# peripherals.net
KiCad netlist of a schematic drawn in Altium Designer
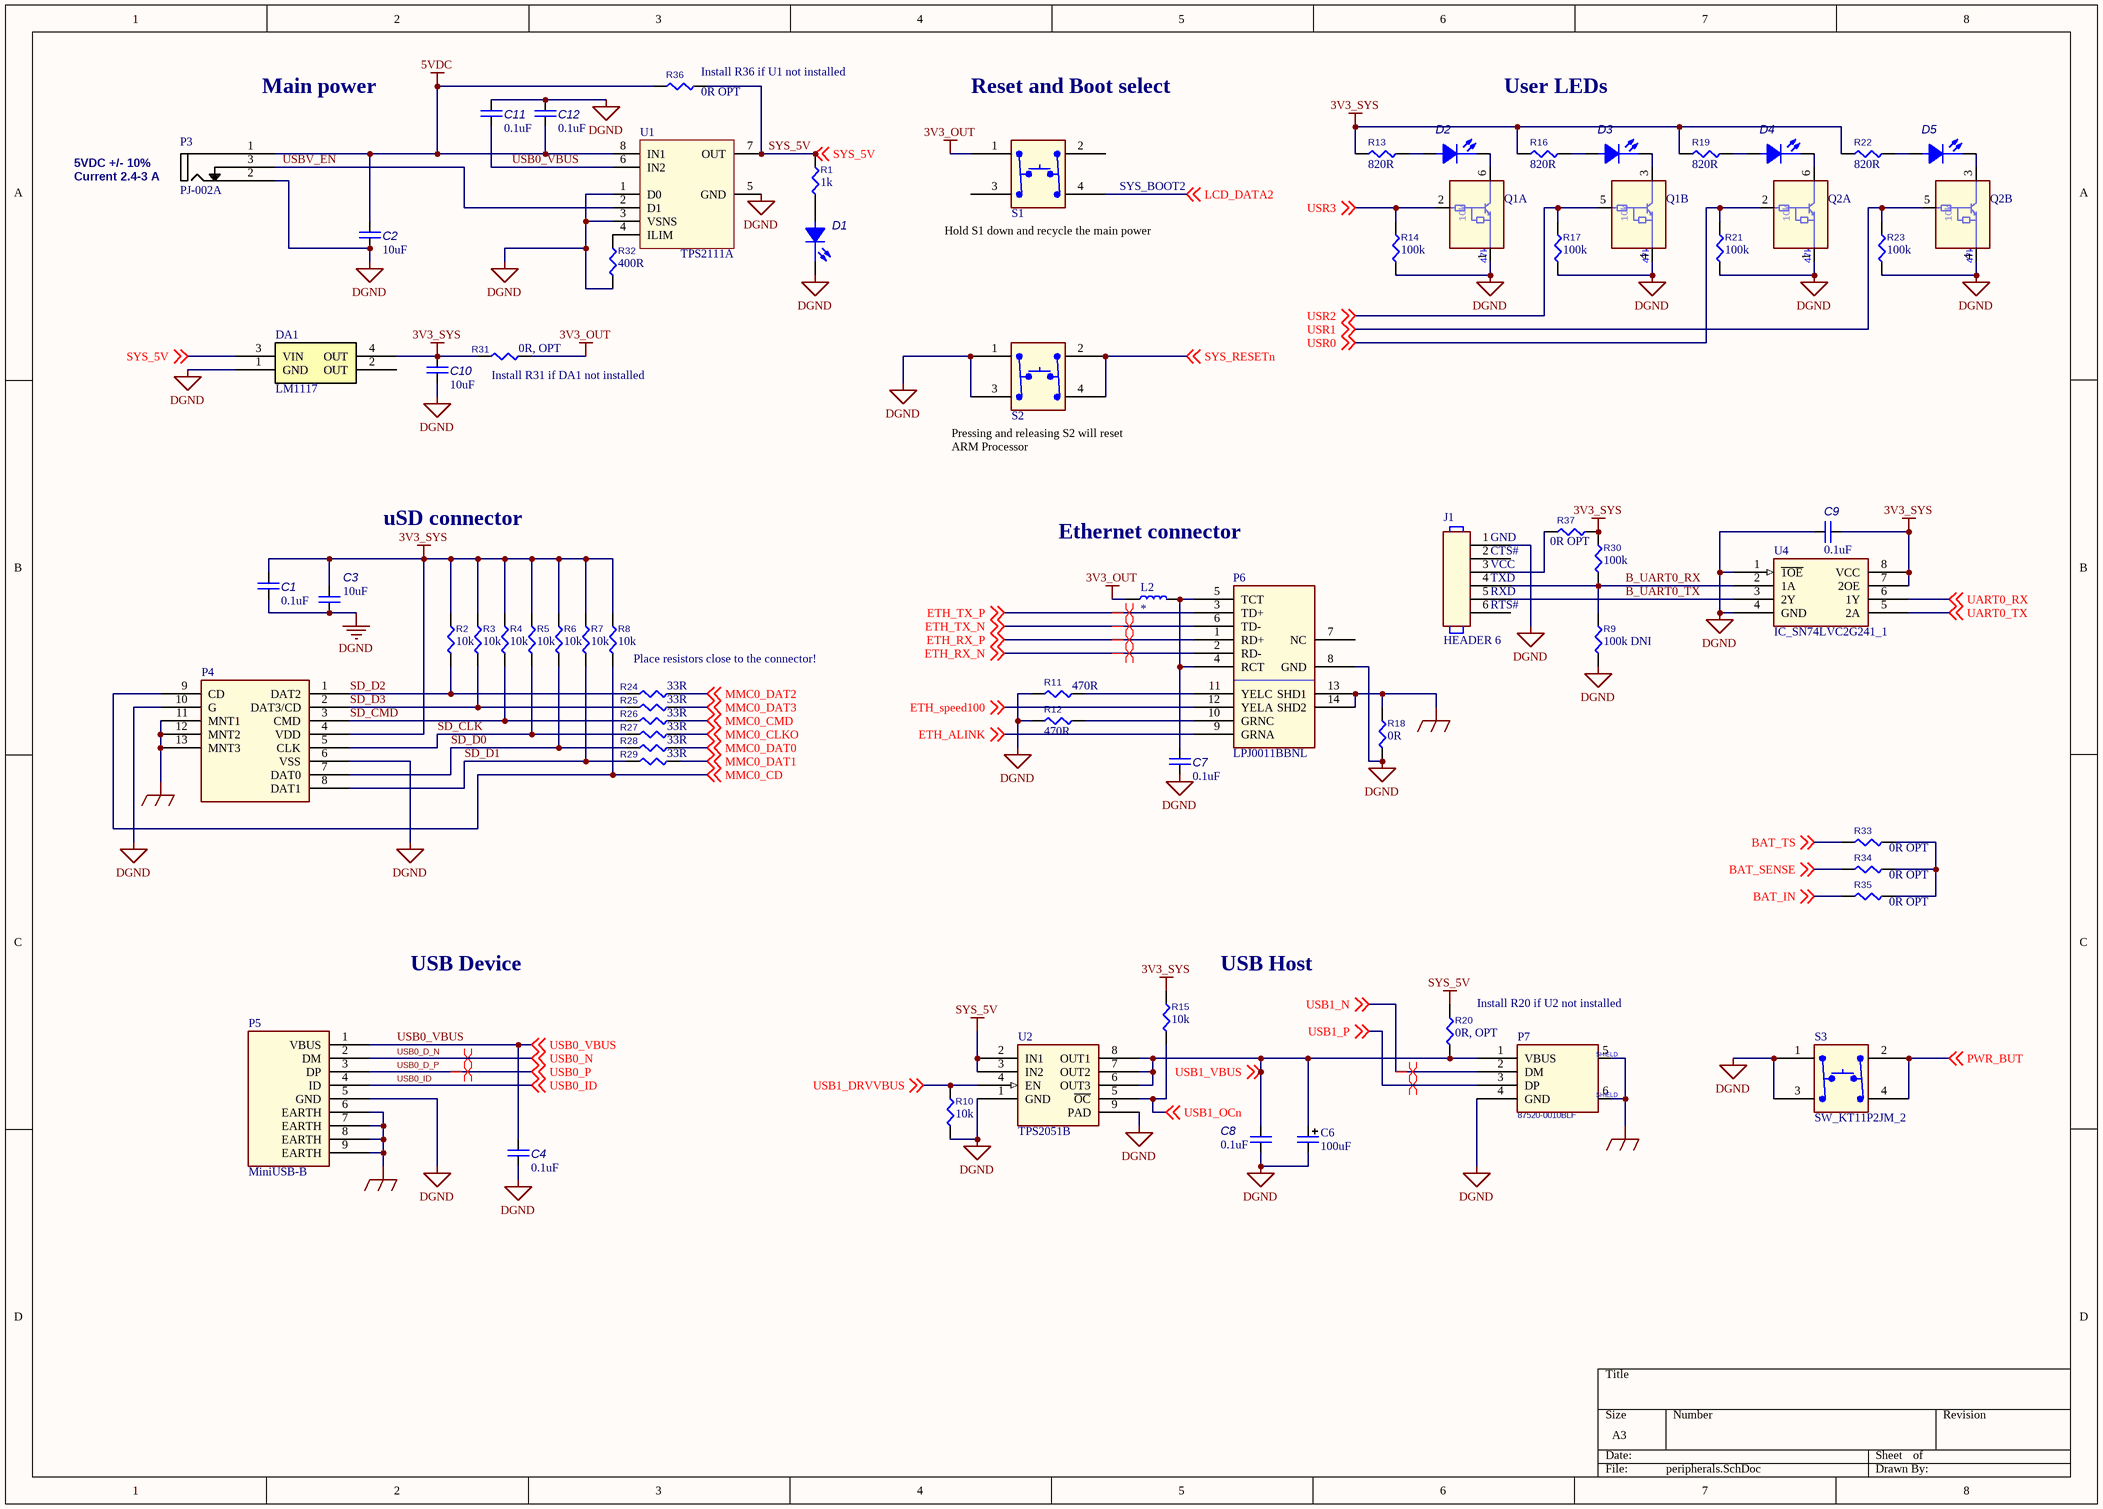
[diagram p0: peripherals.SchDoc]

(export (version "E")
  (design (tool "Eeschema 10.0.6"))
  (components
    (comp (ref "C1")
      (value "0.1uF")
      (footprint "CC1608-0603")
      (description "C0603")
      (libsource (lib "am335x-base") (part "C0603"))
    )
    (comp (ref "C2")
      (value "10uF")
      (footprint "CC2012-0805")
      (description "C0805")
      (libsource (lib "am335x-base") (part "C0805"))
    )
    (comp (ref "C3")
      (value "10uF")
      (footprint "CC2012-0805")
      (description "C0805")
      (libsource (lib "am335x-base") (part "C0805"))
    )
    (comp (ref "C4")
      (value "0.1uF")
      (footprint "CC1608-0603")
      (description "C0603")
      (libsource (lib "am335x-base") (part "C0603"))
    )
    (comp (ref "C6")
      (value "100uF")
      (footprint "Cap_C")
      (description "Tantalum Capacitor Case C")
      (fields (field (name "Comment") "Cap_C"))
      (libsource (lib "am335x-base") (part "Cap_C"))
    )
    (comp (ref "C7")
      (value "0.1uF")
      (footprint "CC1608-0603")
      (description "C0603")
      (libsource (lib "am335x-base") (part "C0603"))
    )
    (comp (ref "C8")
      (value "0.1uF")
      (footprint "CC1608-0603")
      (description "C0603")
      (libsource (lib "am335x-base") (part "C0603"))
    )
    (comp (ref "C9")
      (value "0.1uF")
      (footprint "CC1608-0603")
      (description "C0603")
      (libsource (lib "usomiq-base") (part "C0603"))
    )
    (comp (ref "C10")
      (value "10uF")
      (footprint "CC2012-0805")
      (description "C0805")
      (libsource (lib "am335x-base") (part "C0805"))
    )
    (comp (ref "C11")
      (value "0.1uF")
      (footprint "CC1608-0603")
      (description "C0603")
      (libsource (lib "am335x-base") (part "C0603"))
    )
    (comp (ref "C12")
      (value "0.1uF")
      (footprint "CC1608-0603")
      (description "C0603")
      (libsource (lib "am335x-base") (part "C0603"))
    )
    (comp (ref "D1")
      (value "LED0805")
      (footprint "LED0805")
      (description "LED 0805")
      (libsource (lib "am335x-base") (part "LED0805"))
    )
    (comp (ref "D2")
      (value "LED0805")
      (footprint "LED0805")
      (description "LED 0805")
      (libsource (lib "am335x-base") (part "LED0805"))
    )
    (comp (ref "D3")
      (value "LED0805")
      (footprint "LED0805")
      (description "LED 0805")
      (libsource (lib "am335x-base") (part "LED0805"))
    )
    (comp (ref "D4")
      (value "LED0805")
      (footprint "LED0805")
      (description "LED 0805")
      (libsource (lib "am335x-base") (part "LED0805"))
    )
    (comp (ref "D5")
      (value "LED0805")
      (footprint "LED0805")
      (description "LED 0805")
      (libsource (lib "am335x-base") (part "LED0805"))
    )
    (comp (ref "DA1")
      (value "LM1117")
      (footprint "SOT230P700X160-4N")
      (description "800mA Low-Dropout Linear Regulator")
      (fields (field (name "MANUFACTURER") "National"))
      (libsource (lib "usomiq-base") (part "LM1117"))
    )
    (comp (ref "J1")
      (value "HEADER 6")
      (footprint "DIP6")
      (description "CONN HEADER 6POS, VERTICAL,  .100 STR TIN")
      (fields (field (name "MFR") "FCI"))
      (libsource (lib "usomiq-base") (part "HEADER 6"))
    )
    (comp (ref "L2")
      (value "BLM18A-FB")
      (footprint "CHIP0603")
      (description "Chip EMIFILr Inductor Type")
      (fields (field (name "MANUFACTURER") "Murata") (field (name "MAN P/N") "*"))
      (libsource (lib "am335x-base") (part "BLM18A-FB"))
    )
    (comp (ref "P3")
      (value "PJ-002A")
      (footprint "PJ-002A")
      (description "DC POWER JACK")
      (fields (field (name "MANUFACTURER") "CIU Inc"))
      (libsource (lib "omap") (part "PJ-002A"))
    )
    (comp (ref "P4")
      (value "~")
      (footprint "TFC08WP01F-A-R1K-H")
      (description "Connector for microSD™ Card (Push-push Type)")
      (fields (field (name "MFR") "AUK Contractors Co, LTD"))
      (libsource (lib "usomiq-base") (part "TFC08WP01F-R1K-H-CN"))
    )
    (comp (ref "P5")
      (value "MiniUSB-B")
      (footprint "MINI-USB-B5 SMT")
      (description "Mini USB Type B CONNECTOR")
      (fields (field (name "MFR") "Hirose"))
      (libsource (lib "usomiq-base") (part "MiniUSB-B"))
    )
    (comp (ref "P6")
      (value "CONN_RJ45_MAG_WE_0")
      (footprint "TRJ0011ABNL")
      (description "RJ-45 10/100 W/Magnetics")
      (fields (field (name "MFR") "Link PP") (field (name "P/N") "LPJ0011BBNL"))
      (libsource (lib "am335x-base") (part "CONN_RJ45_MAG_WE_0"))
    )
    (comp (ref "P7")
      (value "CONN_54819-0578_2")
      (footprint "USB2.5-2H4C")
      (description "USB Type A Connectors")
      (fields (field (name "P/N") "87520-0010BLF") (field (name "MFR") "FCI"))
      (libsource (lib "am335x-base") (part "CONN_54819-0578_2"))
    )
    (comp (ref "Q1")
      (value "RN1907")
      (footprint "SOT363-6L")
      (description "Transistor Silicon NPN")
      (fields (field (name "MFR") "ONS"))
      (libsource (lib "usomiq-base") (part "RN1907"))
    )
    (comp (ref "Q2")
      (value "RN1907")
      (footprint "SOT363-6L")
      (description "Transistor Silicon NPN")
      (fields (field (name "MFR") "ONS"))
      (libsource (lib "usomiq-base") (part "RN1907"))
    )
    (comp (ref "R1")
      (value "1k")
      (footprint "RESC1608X55N")
      (description "R0603")
      (libsource (lib "am335x-base") (part "R0603"))
    )
    (comp (ref "R2")
      (value "10k")
      (footprint "RESC1608X55N")
      (description "R0603")
      (libsource (lib "am335x-base") (part "R0603"))
    )
    (comp (ref "R3")
      (value "10k")
      (footprint "RESC1608X55N")
      (description "R0603")
      (libsource (lib "am335x-base") (part "R0603"))
    )
    (comp (ref "R4")
      (value "10k")
      (footprint "RESC1608X55N")
      (description "R0603")
      (libsource (lib "am335x-base") (part "R0603"))
    )
    (comp (ref "R5")
      (value "10k")
      (footprint "RESC1608X55N")
      (description "R0603")
      (libsource (lib "am335x-base") (part "R0603"))
    )
    (comp (ref "R6")
      (value "10k")
      (footprint "RESC1608X55N")
      (description "R0603")
      (libsource (lib "am335x-base") (part "R0603"))
    )
    (comp (ref "R7")
      (value "10k")
      (footprint "RESC1608X55N")
      (description "R0603")
      (libsource (lib "am335x-base") (part "R0603"))
    )
    (comp (ref "R8")
      (value "10k")
      (footprint "RESC1608X55N")
      (description "R0603")
      (libsource (lib "am335x-base") (part "R0603"))
    )
    (comp (ref "R9")
      (value "100k DNI")
      (footprint "RESC1608X55N")
      (description "R0603")
      (libsource (lib "am335x-base") (part "R0603"))
    )
    (comp (ref "R10")
      (value "10k")
      (footprint "RESC1608X55N")
      (description "R0603")
      (libsource (lib "am335x-base") (part "R0603"))
    )
    (comp (ref "R11")
      (value "470R")
      (footprint "RESC1608X55N")
      (description "R0603")
      (libsource (lib "am335x-base") (part "R0603"))
    )
    (comp (ref "R12")
      (value "470R")
      (footprint "RESC1608X55N")
      (description "R0603")
      (libsource (lib "am335x-base") (part "R0603"))
    )
    (comp (ref "R13")
      (value "820R")
      (footprint "RESC1608X55N")
      (description "R0603")
      (libsource (lib "am335x-base") (part "R0603"))
    )
    (comp (ref "R14")
      (value "100k")
      (footprint "RESC1608X55N")
      (description "R0603")
      (libsource (lib "am335x-base") (part "R0603"))
    )
    (comp (ref "R15")
      (value "10k")
      (footprint "RESC1608X55N")
      (description "R0603")
      (libsource (lib "am335x-base") (part "R0603"))
    )
    (comp (ref "R16")
      (value "820R")
      (footprint "RESC1608X55N")
      (description "R0603")
      (libsource (lib "am335x-base") (part "R0603"))
    )
    (comp (ref "R17")
      (value "100k")
      (footprint "RESC1608X55N")
      (description "R0603")
      (libsource (lib "am335x-base") (part "R0603"))
    )
    (comp (ref "R18")
      (value "0R")
      (footprint "RESC1608X55N")
      (description "R0603")
      (libsource (lib "am335x-base") (part "R0603"))
    )
    (comp (ref "R19")
      (value "820R")
      (footprint "RESC1608X55N")
      (description "R0603")
      (libsource (lib "am335x-base") (part "R0603"))
    )
    (comp (ref "R20")
      (value "0R, OPT")
      (footprint "RESC1608X55N")
      (description "R0603")
      (libsource (lib "am335x-base") (part "R0603"))
    )
    (comp (ref "R21")
      (value "100k")
      (footprint "RESC1608X55N")
      (description "R0603")
      (libsource (lib "am335x-base") (part "R0603"))
    )
    (comp (ref "R22")
      (value "820R")
      (footprint "RESC1608X55N")
      (description "R0603")
      (libsource (lib "am335x-base") (part "R0603"))
    )
    (comp (ref "R23")
      (value "100k")
      (footprint "RESC1608X55N")
      (description "R0603")
      (libsource (lib "am335x-base") (part "R0603"))
    )
    (comp (ref "R24")
      (value "33R")
      (footprint "RESC1608X55N")
      (description "R0603")
      (libsource (lib "usomiq-base") (part "R0603"))
    )
    (comp (ref "R25")
      (value "33R")
      (footprint "RESC1608X55N")
      (description "R0603")
      (libsource (lib "usomiq-base") (part "R0603"))
    )
    (comp (ref "R26")
      (value "33R")
      (footprint "RESC1608X55N")
      (description "R0603")
      (libsource (lib "usomiq-base") (part "R0603"))
    )
    (comp (ref "R27")
      (value "33R")
      (footprint "RESC1608X55N")
      (description "R0603")
      (libsource (lib "usomiq-base") (part "R0603"))
    )
    (comp (ref "R28")
      (value "33R")
      (footprint "RESC1608X55N")
      (description "R0603")
      (libsource (lib "usomiq-base") (part "R0603"))
    )
    (comp (ref "R29")
      (value "33R")
      (footprint "RESC1608X55N")
      (description "R0603")
      (libsource (lib "usomiq-base") (part "R0603"))
    )
    (comp (ref "R30")
      (value "100k")
      (footprint "RESC1608X55N")
      (description "R0603")
      (libsource (lib "am335x-base") (part "R0603"))
    )
    (comp (ref "R31")
      (value "0R, OPT")
      (footprint "RESC1608X55N")
      (description "R0603")
      (libsource (lib "usomiq-base") (part "R0603"))
    )
    (comp (ref "R32")
      (value "400R")
      (footprint "RESC1608X55N")
      (description "R0603")
      (libsource (lib "usomiq-base") (part "R0603"))
    )
    (comp (ref "R33")
      (value "0R OPT")
      (footprint "RESC1608X55N")
      (description "R0603")
      (libsource (lib "usomiq-base") (part "R0603"))
    )
    (comp (ref "R34")
      (value "0R OPT")
      (footprint "RESC1608X55N")
      (description "R0603")
      (libsource (lib "usomiq-base") (part "R0603"))
    )
    (comp (ref "R35")
      (value "0R OPT")
      (footprint "RESC1608X55N")
      (description "R0603")
      (libsource (lib "usomiq-base") (part "R0603"))
    )
    (comp (ref "R36")
      (value "0R OPT")
      (footprint "RESC1608X55N")
      (description "R0603")
      (libsource (lib "usomiq-base") (part "R0603"))
    )
    (comp (ref "R37")
      (value "0R OPT")
      (footprint "RESC1608X55N")
      (description "R0603")
      (libsource (lib "usomiq-base") (part "R0603"))
    )
    (comp (ref "S1")
      (value "SW_KT11P2JM_2")
      (footprint "KMR231GLFS")
      (description "SMD button")
      (fields (field (name "MFR") "C&K Components"))
      (libsource (lib "usomiq-base") (part "SW_KT11P2JM_2"))
    )
    (comp (ref "S2")
      (value "SW_KT11P2JM_2")
      (footprint "KMR231GLFS")
      (description "SMD button")
      (fields (field (name "MFR") "C&K Components"))
      (libsource (lib "usomiq-base") (part "SW_KT11P2JM_2"))
    )
    (comp (ref "S3")
      (value "SW_KT11P2JM_2")
      (footprint "KMR231GLFS")
      (description "SMD button")
      (fields (field (name "MFR") "C&K Components"))
      (libsource (lib "usomiq-base") (part "SW_KT11P2JM_2"))
    )
    (comp (ref "U1")
      (value "TPS211xA")
      (footprint "TSSOP-8")
      (description "Single Channel, Current-Limited USB Power Distribution Switch")
      (fields (field (name "MANUFACTURER") "TI") (field (name "P/N") "TPS2111A"))
      (libsource (lib "usomiq-base") (part "TPS211xA"))
    )
    (comp (ref "U2")
      (value "TPS2051B")
      (footprint "R-PDSO-G8")
      (description "CURRENT-LIMITED, POWER-DISTRIBUTION SWITCHES")
      (fields (field (name "MFR") "TI"))
      (libsource (lib "usomiq-base") (part "TPS2051B"))
    )
    (comp (ref "U4")
      (value "IC_SN74LVC2G241_1")
      (footprint "SOP127P600-8N")
      (description "Dual Buffer/Driver With 3-State Outputs")
      (fields (field (name "MFR") "TI"))
      (libsource (lib "usomiq-base") (part "IC_SN74LVC2G241_1"))
    )
  )
  (nets
    (net (code "1") (name "/B_UART0_RX") (class "Default")
      (node (ref "J1") (pin "4") (pinfunction "4_4") (pintype "passive"))
      (node (ref "R30") (pin "1") (pinfunction "1_1") (pintype "passive"))
      (node (ref "R9") (pin "2") (pinfunction "2_2") (pintype "passive"))
      (node (ref "U4") (pin "2") (pinfunction "1A_2") (pintype "passive"))
    )
    (net (code "2") (name "/B_UART0_TX") (class "Default")
      (node (ref "J1") (pin "5") (pinfunction "5_5") (pintype "passive"))
      (node (ref "U4") (pin "3") (pinfunction "2Y_3") (pintype "passive"))
    )
    (net (code "3") (name "/SD_CLK") (class "Default")
      (node (ref "P4") (pin "5") (pinfunction "CLK_5") (pintype "passive"))
      (node (ref "R27") (pin "1") (pinfunction "1_1") (pintype "passive"))
      (node (ref "R5") (pin "1") (pinfunction "1_1") (pintype "passive"))
    )
    (net (code "4") (name "/SD_CMD") (class "Default")
      (node (ref "P4") (pin "3") (pinfunction "CMD_3") (pintype "passive"))
      (node (ref "R26") (pin "1") (pinfunction "1_1") (pintype "passive"))
      (node (ref "R4") (pin "1") (pinfunction "1_1") (pintype "passive"))
    )
    (net (code "5") (name "/SD_D0") (class "Default")
      (node (ref "P4") (pin "7") (pinfunction "DAT0_7") (pintype "passive"))
      (node (ref "R28") (pin "1") (pinfunction "1_1") (pintype "passive"))
      (node (ref "R6") (pin "1") (pinfunction "1_1") (pintype "passive"))
    )
    (net (code "6") (name "/SD_D1") (class "Default")
      (node (ref "P4") (pin "8") (pinfunction "DAT1_8") (pintype "passive"))
      (node (ref "R29") (pin "1") (pinfunction "1_1") (pintype "passive"))
      (node (ref "R7") (pin "1") (pinfunction "1_1") (pintype "passive"))
    )
    (net (code "7") (name "/SD_D2") (class "Default")
      (node (ref "P4") (pin "1") (pinfunction "DAT2_1") (pintype "passive"))
      (node (ref "R2") (pin "1") (pinfunction "1_1") (pintype "passive"))
      (node (ref "R24") (pin "1") (pinfunction "1_1") (pintype "passive"))
    )
    (net (code "8") (name "/SD_D3") (class "Default")
      (node (ref "P4") (pin "2") (pinfunction "DAT3/CD_2") (pintype "passive"))
      (node (ref "R25") (pin "1") (pinfunction "1_1") (pintype "passive"))
      (node (ref "R3") (pin "1") (pinfunction "1_1") (pintype "passive"))
    )
    (net (code "9") (name "/USBV_EN") (class "Default")
      (node (ref "P3") (pin "3") (pinfunction "LEFT_3") (pintype "passive"))
      (node (ref "U1") (pin "2") (pinfunction "D1_2") (pintype "passive"))
    )
    (net (code "10") (name "3V3_OUT") (class "Default")
      (node (ref "L2") (pin "1") (pinfunction "1_1") (pintype "passive"))
      (node (ref "R31") (pin "2") (pinfunction "2_2") (pintype "passive"))
      (node (ref "S1") (pin "1") (pinfunction "A1_1") (pintype "passive"))
    )
    (net (code "11") (name "3V3_SYS") (class "Default")
      (node (ref "C1") (pin "1") (pinfunction "1_1") (pintype "passive"))
      (node (ref "C10") (pin "2") (pinfunction "2_2") (pintype "passive"))
      (node (ref "C3") (pin "2") (pinfunction "2_2") (pintype "passive"))
      (node (ref "C9") (pin "2") (pinfunction "2_2") (pintype "passive"))
      (node (ref "DA1") (pin "4") (pinfunction "OUT_4") (pintype "power_in"))
      (node (ref "P4") (pin "4") (pinfunction "VDD_4") (pintype "power_in"))
      (node (ref "R13") (pin "2") (pinfunction "2_2") (pintype "passive"))
      (node (ref "R15") (pin "2") (pinfunction "2_2") (pintype "passive"))
      (node (ref "R16") (pin "2") (pinfunction "2_2") (pintype "passive"))
      (node (ref "R19") (pin "2") (pinfunction "2_2") (pintype "passive"))
      (node (ref "R2") (pin "2") (pinfunction "2_2") (pintype "passive"))
      (node (ref "R22") (pin "2") (pinfunction "2_2") (pintype "passive"))
      (node (ref "R3") (pin "2") (pinfunction "2_2") (pintype "passive"))
      (node (ref "R30") (pin "2") (pinfunction "2_2") (pintype "passive"))
      (node (ref "R31") (pin "1") (pinfunction "1_1") (pintype "passive"))
      (node (ref "R37") (pin "2") (pinfunction "2_2") (pintype "passive"))
      (node (ref "R4") (pin "2") (pinfunction "2_2") (pintype "passive"))
      (node (ref "R5") (pin "2") (pinfunction "2_2") (pintype "passive"))
      (node (ref "R6") (pin "2") (pinfunction "2_2") (pintype "passive"))
      (node (ref "R7") (pin "2") (pinfunction "2_2") (pintype "passive"))
      (node (ref "R8") (pin "2") (pinfunction "2_2") (pintype "passive"))
      (node (ref "U4") (pin "7") (pinfunction "2OE_7") (pintype "passive"))
      (node (ref "U4") (pin "8") (pinfunction "VCC_8") (pintype "power_in"))
    )
    (net (code "12") (name "5VDC") (class "Default")
      (node (ref "C12") (pin "2") (pinfunction "2_2") (pintype "passive"))
      (node (ref "C2") (pin "2") (pinfunction "2_2") (pintype "passive"))
      (node (ref "P3") (pin "1") (pinfunction "GND_1") (pintype "passive"))
      (node (ref "R36") (pin "1") (pinfunction "1_1") (pintype "passive"))
      (node (ref "U1") (pin "8") (pinfunction "IN1_8") (pintype "passive"))
    )
    (net (code "13") (name "BAT_IN") (class "Default")
      (node (ref "R35") (pin "1") (pinfunction "1_1") (pintype "passive"))
    )
    (net (code "14") (name "BAT_SENSE") (class "Default")
      (node (ref "R34") (pin "1") (pinfunction "1_1") (pintype "passive"))
    )
    (net (code "15") (name "BAT_TS") (class "Default")
      (node (ref "R33") (pin "1") (pinfunction "1_1") (pintype "passive"))
    )
    (net (code "16") (name "DGND") (class "Default")
      (node (ref "C1") (pin "2") (pinfunction "2_2") (pintype "passive"))
      (node (ref "C10") (pin "1") (pinfunction "1_1") (pintype "passive"))
      (node (ref "C11") (pin "1") (pinfunction "1_1") (pintype "passive"))
      (node (ref "C12") (pin "1") (pinfunction "1_1") (pintype "passive"))
      (node (ref "C2") (pin "1") (pinfunction "1_1") (pintype "passive"))
      (node (ref "C3") (pin "1") (pinfunction "1_1") (pintype "passive"))
      (node (ref "C4") (pin "2") (pinfunction "2_2") (pintype "passive"))
      (node (ref "C6") (pin "2") (pinfunction "2_2") (pintype "passive"))
      (node (ref "C7") (pin "2") (pinfunction "2_2") (pintype "passive"))
      (node (ref "C8") (pin "1") (pinfunction "1_1") (pintype "passive"))
      (node (ref "C9") (pin "1") (pinfunction "1_1") (pintype "passive"))
      (node (ref "D1") (pin "2") (pinfunction "C_2") (pintype "passive"))
      (node (ref "DA1") (pin "1") (pinfunction "GND_1") (pintype "power_in"))
      (node (ref "J1") (pin "1") (pinfunction "1_1") (pintype "passive"))
      (node (ref "P3") (pin "2") (pinfunction "RIGHT_2") (pintype "passive"))
      (node (ref "P4") (pin "10") (pinfunction "G_10") (pintype "passive"))
      (node (ref "P4") (pin "6") (pinfunction "VSS_6") (pintype "power_in"))
      (node (ref "P5") (pin "5") (pinfunction "GND_5") (pintype "power_in"))
      (node (ref "P6") (pin "8") (pinfunction "GND_8") (pintype "passive"))
      (node (ref "P7") (pin "4") (pinfunction "GND_4") (pintype "passive"))
      (node (ref "Q1") (pin "1") (pinfunction "4_1") (pintype "passive"))
      (node (ref "Q1") (pin "4") (pinfunction "4_4") (pintype "passive"))
      (node (ref "Q2") (pin "1") (pinfunction "4_1") (pintype "passive"))
      (node (ref "Q2") (pin "4") (pinfunction "4_4") (pintype "passive"))
      (node (ref "R10") (pin "1") (pinfunction "1_1") (pintype "passive"))
      (node (ref "R11") (pin "1") (pinfunction "1_1") (pintype "passive"))
      (node (ref "R12") (pin "1") (pinfunction "1_1") (pintype "passive"))
      (node (ref "R14") (pin "1") (pinfunction "1_1") (pintype "passive"))
      (node (ref "R17") (pin "1") (pinfunction "1_1") (pintype "passive"))
      (node (ref "R18") (pin "1") (pinfunction "1_1") (pintype "passive"))
      (node (ref "R21") (pin "1") (pinfunction "1_1") (pintype "passive"))
      (node (ref "R23") (pin "1") (pinfunction "1_1") (pintype "passive"))
      (node (ref "R32") (pin "2") (pinfunction "2_2") (pintype "passive"))
      (node (ref "R9") (pin "1") (pinfunction "1_1") (pintype "passive"))
      (node (ref "S2") (pin "1") (pinfunction "A1_1") (pintype "passive"))
      (node (ref "S2") (pin "3") (pinfunction "A2_3") (pintype "passive"))
      (node (ref "S3") (pin "1") (pinfunction "A1_1") (pintype "passive"))
      (node (ref "S3") (pin "3") (pinfunction "A2_3") (pintype "passive"))
      (node (ref "U1") (pin "1") (pinfunction "D0_1") (pintype "passive"))
      (node (ref "U1") (pin "3") (pinfunction "VSNS_3") (pintype "passive"))
      (node (ref "U1") (pin "5") (pinfunction "GND_5") (pintype "passive"))
      (node (ref "U2") (pin "1") (pinfunction "GND_1") (pintype "power_in"))
      (node (ref "U2") (pin "9") (pinfunction "PAD_9") (pintype "passive"))
      (node (ref "U4") (pin "1") (pinfunction "~{1OE}_1") (pintype "input"))
      (node (ref "U4") (pin "4") (pinfunction "GND_4") (pintype "power_in"))
    )
    (net (code "17") (name "EARTH") (class "Default")
      (node (ref "P4") (pin "11") (pinfunction "MNT1_11") (pintype "passive"))
      (node (ref "P4") (pin "12") (pinfunction "MNT2_12") (pintype "passive"))
      (node (ref "P4") (pin "13") (pinfunction "MNT3_13") (pintype "passive"))
      (node (ref "P5") (pin "6") (pinfunction "EARTH_6") (pintype "passive"))
      (node (ref "P5") (pin "7") (pinfunction "EARTH_7") (pintype "passive"))
      (node (ref "P5") (pin "8") (pinfunction "EARTH_8") (pintype "passive"))
      (node (ref "P5") (pin "9") (pinfunction "EARTH_9") (pintype "passive"))
      (node (ref "P6") (pin "13") (pinfunction "SHD1_13") (pintype "passive"))
      (node (ref "P6") (pin "14") (pinfunction "SHD2_14") (pintype "passive"))
      (node (ref "P7") (pin "5") (pinfunction "SHELD1_5") (pintype "passive"))
      (node (ref "P7") (pin "6") (pinfunction "PAD4_6") (pintype "passive"))
      (node (ref "R18") (pin "2") (pinfunction "2_2") (pintype "passive"))
    )
    (net (code "18") (name "ETH_ALINK") (class "Default")
      (node (ref "P6") (pin "9") (pinfunction "GRNA_9") (pintype "passive"))
    )
    (net (code "19") (name "ETH_RX_N") (class "Default")
      (node (ref "P6") (pin "2") (pinfunction "RD-_2") (pintype "passive"))
    )
    (net (code "20") (name "ETH_RX_P") (class "Default")
      (node (ref "P6") (pin "1") (pinfunction "RD+_1") (pintype "passive"))
    )
    (net (code "21") (name "ETH_TX_N") (class "Default")
      (node (ref "P6") (pin "6") (pinfunction "TD-_6") (pintype "passive"))
    )
    (net (code "22") (name "ETH_TX_P") (class "Default")
      (node (ref "P6") (pin "3") (pinfunction "TD+_3") (pintype "passive"))
    )
    (net (code "23") (name "ETH_speed100") (class "Default")
      (node (ref "P6") (pin "12") (pinfunction "YELA_12") (pintype "passive"))
    )
    (net (code "24") (name "LCD_DATA2") (class "Default")
      (node (ref "S1") (pin "4") (pinfunction "B2_4") (pintype "passive"))
    )
    (net (code "25") (name "MMC0_CD") (class "Default")
      (node (ref "P4") (pin "9") (pinfunction "CD_9") (pintype "passive"))
      (node (ref "R8") (pin "1") (pinfunction "1_1") (pintype "passive"))
    )
    (net (code "26") (name "MMC0_CLKO") (class "Default")
      (node (ref "R27") (pin "2") (pinfunction "2_2") (pintype "passive"))
    )
    (net (code "27") (name "MMC0_CMD") (class "Default")
      (node (ref "R26") (pin "2") (pinfunction "2_2") (pintype "passive"))
    )
    (net (code "28") (name "MMC0_DAT0") (class "Default")
      (node (ref "R28") (pin "2") (pinfunction "2_2") (pintype "passive"))
    )
    (net (code "29") (name "MMC0_DAT1") (class "Default")
      (node (ref "R29") (pin "2") (pinfunction "2_2") (pintype "passive"))
    )
    (net (code "30") (name "MMC0_DAT2") (class "Default")
      (node (ref "R24") (pin "2") (pinfunction "2_2") (pintype "passive"))
    )
    (net (code "31") (name "MMC0_DAT3") (class "Default")
      (node (ref "R25") (pin "2") (pinfunction "2_2") (pintype "passive"))
    )
    (net (code "32") (name "Net-(D1-A)") (class "Default")
      (node (ref "D1") (pin "1") (pinfunction "A_1") (pintype "passive"))
      (node (ref "R1") (pin "1") (pinfunction "1_1") (pintype "passive"))
    )
    (net (code "33") (name "Net-(D2-A)") (class "Default")
      (node (ref "D2") (pin "1") (pinfunction "A_1") (pintype "passive"))
      (node (ref "R13") (pin "1") (pinfunction "1_1") (pintype "passive"))
    )
    (net (code "34") (name "Net-(D2-C)") (class "Default")
      (node (ref "D2") (pin "2") (pinfunction "C_2") (pintype "passive"))
      (node (ref "Q1") (pin "6") (pinfunction "3_6") (pintype "passive"))
    )
    (net (code "35") (name "Net-(D3-A)") (class "Default")
      (node (ref "D3") (pin "1") (pinfunction "A_1") (pintype "passive"))
      (node (ref "R16") (pin "1") (pinfunction "1_1") (pintype "passive"))
    )
    (net (code "36") (name "Net-(D3-C)") (class "Default")
      (node (ref "D3") (pin "2") (pinfunction "C_2") (pintype "passive"))
      (node (ref "Q1") (pin "3") (pinfunction "3_3") (pintype "passive"))
    )
    (net (code "37") (name "Net-(D4-A)") (class "Default")
      (node (ref "D4") (pin "1") (pinfunction "A_1") (pintype "passive"))
      (node (ref "R19") (pin "1") (pinfunction "1_1") (pintype "passive"))
    )
    (net (code "38") (name "Net-(D4-C)") (class "Default")
      (node (ref "D4") (pin "2") (pinfunction "C_2") (pintype "passive"))
      (node (ref "Q2") (pin "6") (pinfunction "3_6") (pintype "passive"))
    )
    (net (code "39") (name "Net-(D5-A)") (class "Default")
      (node (ref "D5") (pin "1") (pinfunction "A_1") (pintype "passive"))
      (node (ref "R22") (pin "1") (pinfunction "1_1") (pintype "passive"))
    )
    (net (code "40") (name "Net-(D5-C)") (class "Default")
      (node (ref "D5") (pin "2") (pinfunction "C_2") (pintype "passive"))
      (node (ref "Q2") (pin "3") (pinfunction "3_3") (pintype "passive"))
    )
    (net (code "41") (name "Net-(J1-Pad3)") (class "Default")
      (node (ref "J1") (pin "3") (pinfunction "3_3") (pintype "passive"))
      (node (ref "R37") (pin "1") (pinfunction "1_1") (pintype "passive"))
    )
    (net (code "42") (name "Net-(P6-GRNC)") (class "Default")
      (node (ref "P6") (pin "10") (pinfunction "GRNC_10") (pintype "passive"))
      (node (ref "R12") (pin "2") (pinfunction "2_2") (pintype "passive"))
    )
    (net (code "43") (name "Net-(P6-RCT)") (class "Default")
      (node (ref "C7") (pin "1") (pinfunction "1_1") (pintype "passive"))
      (node (ref "L2") (pin "2") (pinfunction "2_2") (pintype "passive"))
      (node (ref "P6") (pin "4") (pinfunction "RCT_4") (pintype "passive"))
      (node (ref "P6") (pin "5") (pinfunction "TCT_5") (pintype "passive"))
    )
    (net (code "44") (name "Net-(P6-YELC)") (class "Default")
      (node (ref "P6") (pin "11") (pinfunction "YELC_11") (pintype "passive"))
      (node (ref "R11") (pin "2") (pinfunction "2_2") (pintype "passive"))
    )
    (net (code "45") (name "Net-(R33-Pad2)") (class "Default")
      (node (ref "R33") (pin "2") (pinfunction "2_2") (pintype "passive"))
      (node (ref "R34") (pin "2") (pinfunction "2_2") (pintype "passive"))
      (node (ref "R35") (pin "2") (pinfunction "2_2") (pintype "passive"))
    )
    (net (code "46") (name "Net-(U1-ILIM)") (class "Default")
      (node (ref "R32") (pin "1") (pinfunction "1_1") (pintype "passive"))
      (node (ref "U1") (pin "4") (pinfunction "ILIM_4") (pintype "passive"))
    )
    (net (code "47") (name "PWR_BUT") (class "Default")
      (node (ref "S3") (pin "2") (pinfunction "B1_2") (pintype "passive"))
      (node (ref "S3") (pin "4") (pinfunction "B2_4") (pintype "passive"))
    )
    (net (code "48") (name "SYS_5V") (class "Default")
      (node (ref "DA1") (pin "3") (pinfunction "VIN_3") (pintype "power_in"))
      (node (ref "R1") (pin "2") (pinfunction "2_2") (pintype "passive"))
      (node (ref "R20") (pin "2") (pinfunction "2_2") (pintype "passive"))
      (node (ref "R36") (pin "2") (pinfunction "2_2") (pintype "passive"))
      (node (ref "U1") (pin "7") (pinfunction "OUT_7") (pintype "passive"))
      (node (ref "U2") (pin "2") (pinfunction "IN1_2") (pintype "power_in"))
      (node (ref "U2") (pin "3") (pinfunction "IN2_3") (pintype "power_in"))
    )
    (net (code "49") (name "SYS_RESETn") (class "Default")
      (node (ref "S2") (pin "2") (pinfunction "B1_2") (pintype "passive"))
      (node (ref "S2") (pin "4") (pinfunction "B2_4") (pintype "passive"))
    )
    (net (code "50") (name "UART0_RX") (class "Default")
      (node (ref "U4") (pin "6") (pinfunction "1Y_6") (pintype "passive"))
    )
    (net (code "51") (name "UART0_TX") (class "Default")
      (node (ref "U4") (pin "5") (pinfunction "2A_5") (pintype "passive"))
    )
    (net (code "52") (name "USB0_ID") (class "Default")
      (node (ref "P5") (pin "4") (pinfunction "ID_4") (pintype "passive"))
    )
    (net (code "53") (name "USB0_N") (class "Default")
      (node (ref "P5") (pin "2") (pinfunction "DM_2") (pintype "passive"))
    )
    (net (code "54") (name "USB0_P") (class "Default")
      (node (ref "P5") (pin "3") (pinfunction "DP_3") (pintype "passive"))
    )
    (net (code "55") (name "USB0_VBUS") (class "Default")
      (node (ref "C11") (pin "2") (pinfunction "2_2") (pintype "passive"))
      (node (ref "C4") (pin "1") (pinfunction "1_1") (pintype "passive"))
      (node (ref "P5") (pin "1") (pinfunction "VBUS_1") (pintype "power_in"))
      (node (ref "U1") (pin "6") (pinfunction "IN2_6") (pintype "passive"))
    )
    (net (code "56") (name "USB1_DRVVBUS") (class "Default")
      (node (ref "R10") (pin "2") (pinfunction "2_2") (pintype "passive"))
      (node (ref "U2") (pin "4") (pinfunction "EN_4") (pintype "input"))
    )
    (net (code "57") (name "USB1_N") (class "Default")
      (node (ref "P7") (pin "2") (pinfunction "DM_2") (pintype "passive"))
    )
    (net (code "58") (name "USB1_OCn") (class "Default")
      (node (ref "R15") (pin "1") (pinfunction "1_1") (pintype "passive"))
      (node (ref "U2") (pin "5") (pinfunction "~{OC}_5") (pintype "passive"))
    )
    (net (code "59") (name "USB1_P") (class "Default")
      (node (ref "P7") (pin "3") (pinfunction "DP_3") (pintype "passive"))
    )
    (net (code "60") (name "USB1_VBUS") (class "Default")
      (node (ref "C6") (pin "1") (pinfunction "1_1") (pintype "passive"))
      (node (ref "C8") (pin "2") (pinfunction "2_2") (pintype "passive"))
      (node (ref "P7") (pin "1") (pinfunction "VBUS_1") (pintype "passive"))
      (node (ref "R20") (pin "1") (pinfunction "1_1") (pintype "passive"))
      (node (ref "U2") (pin "6") (pinfunction "OUT3_6") (pintype "power_in"))
      (node (ref "U2") (pin "7") (pinfunction "OUT2_7") (pintype "power_in"))
      (node (ref "U2") (pin "8") (pinfunction "OUT1_8") (pintype "power_in"))
    )
    (net (code "61") (name "USR0") (class "Default")
      (node (ref "Q2") (pin "2") (pinfunction "5_2") (pintype "passive"))
      (node (ref "R21") (pin "2") (pinfunction "2_2") (pintype "passive"))
    )
    (net (code "62") (name "USR1") (class "Default")
      (node (ref "Q2") (pin "5") (pinfunction "5_5") (pintype "passive"))
      (node (ref "R23") (pin "2") (pinfunction "2_2") (pintype "passive"))
    )
    (net (code "63") (name "USR2") (class "Default")
      (node (ref "Q1") (pin "5") (pinfunction "5_5") (pintype "passive"))
      (node (ref "R17") (pin "2") (pinfunction "2_2") (pintype "passive"))
    )
    (net (code "64") (name "USR3") (class "Default")
      (node (ref "Q1") (pin "2") (pinfunction "5_2") (pintype "passive"))
      (node (ref "R14") (pin "2") (pinfunction "2_2") (pintype "passive"))
    )
    (net (code "65") (name "unconnected-(DA1-OUT-Pad2)") (class "Default")
      (node (ref "DA1") (pin "2") (pinfunction "OUT_2") (pintype "power_in"))
    )
    (net (code "66") (name "unconnected-(J1-Pad2)") (class "Default")
      (node (ref "J1") (pin "2") (pinfunction "2_2") (pintype "passive"))
    )
    (net (code "67") (name "unconnected-(J1-Pad6)") (class "Default")
      (node (ref "J1") (pin "6") (pinfunction "6_6") (pintype "passive"))
    )
    (net (code "68") (name "unconnected-(P6-NC-Pad7)") (class "Default")
      (node (ref "P6") (pin "7") (pinfunction "NC_7") (pintype "passive"))
    )
    (net (code "69") (name "unconnected-(S1-A2-Pad3)") (class "Default")
      (node (ref "S1") (pin "3") (pinfunction "A2_3") (pintype "passive"))
    )
    (net (code "70") (name "unconnected-(S1-B1-Pad2)") (class "Default")
      (node (ref "S1") (pin "2") (pinfunction "B1_2") (pintype "passive"))
    )
  )
)
